# Sheet2.net
KiCad netlist of a schematic drawn in Altium Designer
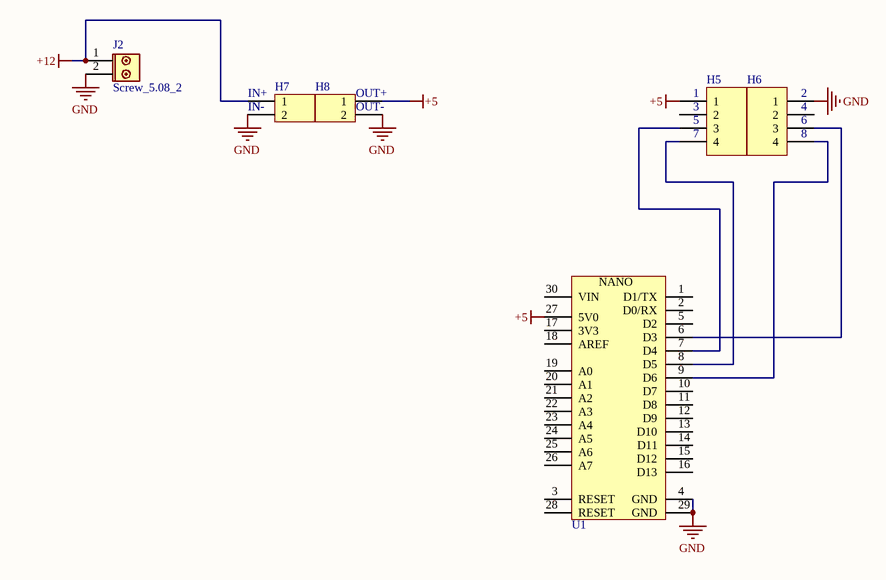
[diagram p0: Sheet2.SchDoc]

(export (version "E")
  (design (tool "Eeschema 10.0.6"))
  (components
    (comp (ref "H5")
      (value "Header 4")
      (footprint "HDR1X4")
      (description "Header, 4-Pin")
      (fields (field (name "MANUFACTURER") "Generic Components"))
      (libsource (lib "") (part "Header 4_1"))
    )
    (comp (ref "H6")
      (value "Header 4")
      (footprint "HDR1X4")
      (description "Header, 4-Pin")
      (fields (field (name "MANUFACTURER") "Generic Components"))
      (libsource (lib "MasseyLibs") (part "Header 4"))
    )
    (comp (ref "H7")
      (value "Header 2")
      (footprint "HDR1X2")
      (description "Header, 2-Pin")
      (fields (field (name "MANUFACTURER") "Generic Components"))
      (libsource (lib "MasseyLibs") (part "Header 2"))
    )
    (comp (ref "H8")
      (value "Header 2")
      (footprint "HDR1X2")
      (description "Header, 2-Pin")
      (fields (field (name "MANUFACTURER") "Generic Components"))
      (libsource (lib "") (part "Header 2_1"))
    )
    (comp (ref "J2")
      (value "Screw_5.08_2")
      (footprint "ScrewTerm_2.54_2")
      (description "2 way screw terminal connector")
      (libsource (lib "MasseyLibs") (part "Screw_5.08_2"))
    )
    (comp (ref "U1")
      (value "Arduino Nano")
      (footprint "Arduino_NANO")
      (description "DIL Arduino Nano")
      (fields (field (name "PUBLISHER") "Altium Limited"))
      (libsource (lib "MasseyLibs") (part "Arduino Nano"))
    )
  )
  (nets
    (net (code "1") (name "+5") (class "Default")
      (node (ref "H5") (pin "1") (pinfunction "1_1") (pintype "passive"))
      (node (ref "H8") (pin "1") (pinfunction "1_1") (pintype "passive"))
      (node (ref "U1") (pin "27") (pinfunction "5V0_27") (pintype "passive"))
    )
    (net (code "2") (name "+12") (class "Default")
      (node (ref "H7") (pin "1") (pinfunction "1_1") (pintype "passive"))
      (node (ref "J2") (pin "1") (pinfunction "1_1") (pintype "passive"))
    )
    (net (code "3") (name "GND") (class "Default")
      (node (ref "H6") (pin "1") (pinfunction "1_1") (pintype "passive"))
      (node (ref "H7") (pin "2") (pinfunction "2_2") (pintype "passive"))
      (node (ref "H8") (pin "2") (pinfunction "2_2") (pintype "passive"))
      (node (ref "J2") (pin "2") (pinfunction "2_2") (pintype "passive"))
      (node (ref "U1") (pin "29") (pinfunction "GND_29") (pintype "passive"))
      (node (ref "U1") (pin "4") (pinfunction "GND_4") (pintype "passive"))
    )
    (net (code "4") (name "Net-(U1-D3)") (class "Default")
      (node (ref "H6") (pin "3") (pinfunction "3_3") (pintype "passive"))
      (node (ref "U1") (pin "6") (pinfunction "D3_6") (pintype "passive"))
    )
    (net (code "5") (name "Net-(U1-D4)") (class "Default")
      (node (ref "H5") (pin "3") (pinfunction "3_3") (pintype "passive"))
      (node (ref "U1") (pin "7") (pinfunction "D4_7") (pintype "passive"))
    )
    (net (code "6") (name "Net-(U1-D5)") (class "Default")
      (node (ref "H5") (pin "4") (pinfunction "4_4") (pintype "passive"))
      (node (ref "U1") (pin "8") (pinfunction "D5_8") (pintype "passive"))
    )
    (net (code "7") (name "Net-(U1-D6)") (class "Default")
      (node (ref "H6") (pin "4") (pinfunction "4_4") (pintype "passive"))
      (node (ref "U1") (pin "9") (pinfunction "D6_9") (pintype "passive"))
    )
    (net (code "8") (name "unconnected-(H5-Pad2)") (class "Default")
      (node (ref "H5") (pin "2") (pinfunction "2_2") (pintype "passive"))
    )
    (net (code "9") (name "unconnected-(H6-Pad2)") (class "Default")
      (node (ref "H6") (pin "2") (pinfunction "2_2") (pintype "passive"))
    )
    (net (code "10") (name "unconnected-(U1-3V3-Pad17)") (class "Default")
      (node (ref "U1") (pin "17") (pinfunction "3V3_17") (pintype "passive"))
    )
    (net (code "11") (name "unconnected-(U1-A0-Pad19)") (class "Default")
      (node (ref "U1") (pin "19") (pinfunction "A0_19") (pintype "passive"))
    )
    (net (code "12") (name "unconnected-(U1-A1-Pad20)") (class "Default")
      (node (ref "U1") (pin "20") (pinfunction "A1_20") (pintype "passive"))
    )
    (net (code "13") (name "unconnected-(U1-A2-Pad21)") (class "Default")
      (node (ref "U1") (pin "21") (pinfunction "A2_21") (pintype "passive"))
    )
    (net (code "14") (name "unconnected-(U1-A3-Pad22)") (class "Default")
      (node (ref "U1") (pin "22") (pinfunction "A3_22") (pintype "passive"))
    )
    (net (code "15") (name "unconnected-(U1-A4-Pad23)") (class "Default")
      (node (ref "U1") (pin "23") (pinfunction "A4_23") (pintype "passive"))
    )
    (net (code "16") (name "unconnected-(U1-A5-Pad24)") (class "Default")
      (node (ref "U1") (pin "24") (pinfunction "A5_24") (pintype "passive"))
    )
    (net (code "17") (name "unconnected-(U1-A6-Pad25)") (class "Default")
      (node (ref "U1") (pin "25") (pinfunction "A6_25") (pintype "passive"))
    )
    (net (code "18") (name "unconnected-(U1-A7-Pad26)") (class "Default")
      (node (ref "U1") (pin "26") (pinfunction "A7_26") (pintype "passive"))
    )
    (net (code "19") (name "unconnected-(U1-AREF-Pad18)") (class "Default")
      (node (ref "U1") (pin "18") (pinfunction "AREF_18") (pintype "passive"))
    )
    (net (code "20") (name "unconnected-(U1-D0{slash}RX-Pad2)") (class "Default")
      (node (ref "U1") (pin "2") (pinfunction "D0/RX_2") (pintype "passive"))
    )
    (net (code "21") (name "unconnected-(U1-D1{slash}TX-Pad1)") (class "Default")
      (node (ref "U1") (pin "1") (pinfunction "D1/TX_1") (pintype "passive"))
    )
    (net (code "22") (name "unconnected-(U1-D2-Pad5)") (class "Default")
      (node (ref "U1") (pin "5") (pinfunction "D2_5") (pintype "passive"))
    )
    (net (code "23") (name "unconnected-(U1-D7-Pad10)") (class "Default")
      (node (ref "U1") (pin "10") (pinfunction "D7_10") (pintype "passive"))
    )
    (net (code "24") (name "unconnected-(U1-D8-Pad11)") (class "Default")
      (node (ref "U1") (pin "11") (pinfunction "D8_11") (pintype "passive"))
    )
    (net (code "25") (name "unconnected-(U1-D9-Pad12)") (class "Default")
      (node (ref "U1") (pin "12") (pinfunction "D9_12") (pintype "passive"))
    )
    (net (code "26") (name "unconnected-(U1-D10-Pad13)") (class "Default")
      (node (ref "U1") (pin "13") (pinfunction "D10_13") (pintype "passive"))
    )
    (net (code "27") (name "unconnected-(U1-D11-Pad14)") (class "Default")
      (node (ref "U1") (pin "14") (pinfunction "D11_14") (pintype "passive"))
    )
    (net (code "28") (name "unconnected-(U1-D12-Pad15)") (class "Default")
      (node (ref "U1") (pin "15") (pinfunction "D12_15") (pintype "passive"))
    )
    (net (code "29") (name "unconnected-(U1-D13-Pad16)") (class "Default")
      (node (ref "U1") (pin "16") (pinfunction "D13_16") (pintype "passive"))
    )
    (net (code "30") (name "unconnected-(U1-RESET-Pad3)") (class "Default")
      (node (ref "U1") (pin "3") (pinfunction "RESET_3") (pintype "passive"))
    )
    (net (code "31") (name "unconnected-(U1-RESET-Pad28)") (class "Default")
      (node (ref "U1") (pin "28") (pinfunction "RESET_28") (pintype "passive"))
    )
    (net (code "32") (name "unconnected-(U1-VIN-Pad30)") (class "Default")
      (node (ref "U1") (pin "30") (pinfunction "VIN_30") (pintype "passive"))
    )
  )
)
